# okinesio_v02.net
KiCad netlist of a schematic drawn in EAGLE
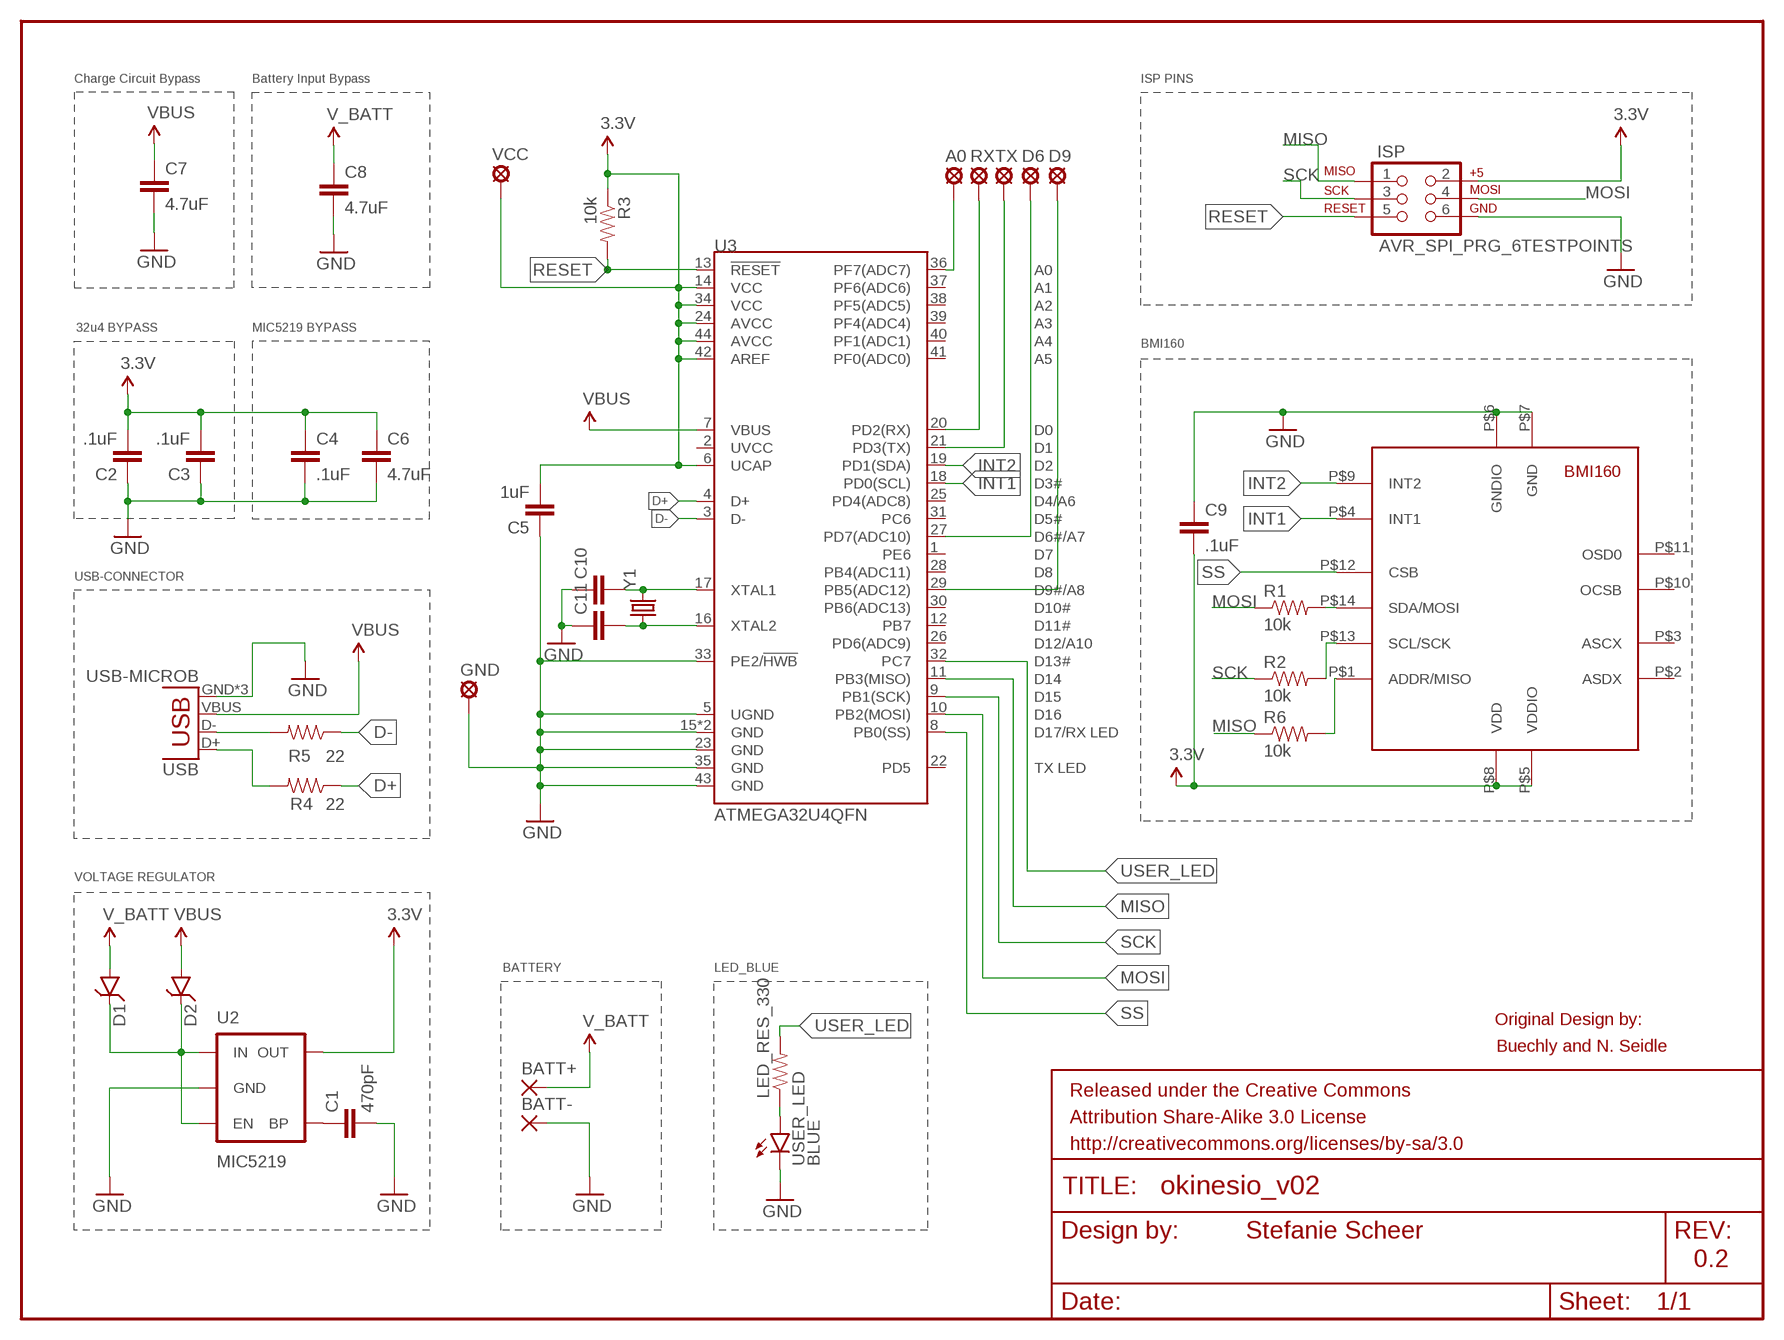
[diagram p0: schematic, sheet 1]

(export (version "E")
  (design (tool "Eeschema 10.0.6"))
  (components
    (comp (ref "A0")
      (value "LSP10")
      (footprint "eagle-import:LSP10")
      (libsource (lib "eagle-import") (part "LSP10"))
    )
    (comp (ref "BATT+")
      (value "SMD2")
      (footprint "eagle-import:SMD1,27-2,54")
      (libsource (lib "eagle-import") (part "SMD2"))
    )
    (comp (ref "BATT-")
      (value "SMD2")
      (footprint "eagle-import:SMD1,27-2,54")
      (libsource (lib "eagle-import") (part "SMD2"))
    )
    (comp (ref "C1")
      (value "470pF")
      (footprint "eagle-import:0603-CAP")
      (libsource (lib "eagle-import") (part "SparkFun-Passives_CAP0603-CAP"))
    )
    (comp (ref "C2")
      (value ".1uF")
      (footprint "eagle-import:0603-CAP")
      (libsource (lib "eagle-import") (part "SparkFun-Passives_CAP0603-CAP"))
    )
    (comp (ref "C3")
      (value ".1uF")
      (footprint "eagle-import:0603-CAP")
      (libsource (lib "eagle-import") (part "SparkFun-Passives_CAP0603-CAP"))
    )
    (comp (ref "C4")
      (value ".1uF")
      (footprint "eagle-import:0603-CAP")
      (libsource (lib "eagle-import") (part "CAP0603-CAP"))
    )
    (comp (ref "C5")
      (value "1uF")
      (footprint "eagle-import:0603-CAP")
      (libsource (lib "eagle-import") (part "SparkFun-Passives_CAP0603-CAP"))
    )
    (comp (ref "C6")
      (value "4.7uF")
      (footprint "eagle-import:0603-CAP")
      (libsource (lib "eagle-import") (part "CAP0603-CAP"))
    )
    (comp (ref "C7")
      (value "4.7uF")
      (footprint "eagle-import:0805")
      (libsource (lib "eagle-import") (part "CAP0805"))
    )
    (comp (ref "C8")
      (value "4.7uF")
      (footprint "eagle-import:0805")
      (libsource (lib "eagle-import") (part "CAP0805"))
    )
    (comp (ref "C9")
      (value ".1uF")
      (footprint "eagle-import:0603-CAP")
      (libsource (lib "eagle-import") (part "SparkFun-Passives_CAP0603-CAP"))
    )
    (comp (ref "C10")
      (value "CAP0603-CAP")
      (footprint "eagle-import:0603-CAP")
      (libsource (lib "eagle-import") (part "CAP0603-CAP"))
    )
    (comp (ref "C11")
      (value "CAP0603-CAP")
      (footprint "eagle-import:0603-CAP")
      (libsource (lib "eagle-import") (part "CAP0603-CAP"))
    )
    (comp (ref "D1")
      (value "DIODESOD123")
      (footprint "eagle-import:SOD-123")
      (libsource (lib "eagle-import") (part "DIODESOD123"))
    )
    (comp (ref "D2")
      (value "DIODESOD123")
      (footprint "eagle-import:SOD-123")
      (libsource (lib "eagle-import") (part "DIODESOD123"))
    )
    (comp (ref "D6")
      (value "LSP10")
      (footprint "eagle-import:LSP10")
      (libsource (lib "eagle-import") (part "LSP10"))
    )
    (comp (ref "D9")
      (value "LSP10")
      (footprint "eagle-import:LSP10")
      (libsource (lib "eagle-import") (part "LSP10"))
    )
    (comp (ref "GND")
      (value "LSP10")
      (footprint "eagle-import:LSP10")
      (libsource (lib "eagle-import") (part "LSP10"))
    )
    (comp (ref "ISP")
      (value "AVR_SPI_PRG_6TESTPOINTS")
      (footprint "eagle-import:2X3_TEST_POINTS")
      (libsource (lib "eagle-import") (part "AVR_SPI_PRG_6TESTPOINTS"))
    )
    (comp (ref "LED_RES_330")
      (value "RESISTOR0603")
      (footprint "eagle-import:0603-RES")
      (libsource (lib "eagle-import") (part "RESISTOR0603"))
    )
    (comp (ref "R1")
      (value "10k")
      (footprint "eagle-import:0603-RES")
      (libsource (lib "eagle-import") (part "RESISTOR0603-RES"))
    )
    (comp (ref "R2")
      (value "10k")
      (footprint "eagle-import:0603-RES")
      (libsource (lib "eagle-import") (part "RESISTOR0603-RES"))
    )
    (comp (ref "R3")
      (value "10k")
      (footprint "eagle-import:0603-RES")
      (libsource (lib "eagle-import") (part "RESISTOR0603-RES"))
    )
    (comp (ref "R4")
      (value "22")
      (footprint "eagle-import:0603-RES")
      (libsource (lib "eagle-import") (part "RESISTOR0603-RES"))
    )
    (comp (ref "R5")
      (value "22")
      (footprint "eagle-import:0603-RES")
      (libsource (lib "eagle-import") (part "RESISTOR0603-RES"))
    )
    (comp (ref "R6")
      (value "10k")
      (footprint "eagle-import:0603-RES")
      (libsource (lib "eagle-import") (part "RESISTOR0603-RES"))
    )
    (comp (ref "RX")
      (value "LSP10")
      (footprint "eagle-import:LSP10")
      (libsource (lib "eagle-import") (part "LSP10"))
    )
    (comp (ref "TX")
      (value "LSP10")
      (footprint "eagle-import:LSP10")
      (libsource (lib "eagle-import") (part "LSP10"))
    )
    (comp (ref "U$3")
      (value "BMI160LGA14")
      (footprint "eagle-import:LGA14-BMI160")
      (libsource (lib "eagle-import") (part "BMI160LGA14"))
    )
    (comp (ref "U2")
      (value "MIC5219")
      (footprint "eagle-import:SOT23-5")
      (libsource (lib "eagle-import") (part "V_REG_MIC5219SMD"))
    )
    (comp (ref "U3")
      (value "ATMEGA32U4QFN")
      (footprint "eagle-import:QFN-44")
      (libsource (lib "eagle-import") (part "ATMEGA32U4QFN"))
    )
    (comp (ref "USB")
      (value "USB-MICROB")
      (footprint "eagle-import:USB-MICROB")
      (libsource (lib "eagle-import") (part "USB-MICROB"))
    )
    (comp (ref "USER_LED")
      (value "BLUE")
      (footprint "eagle-import:LED-0603")
      (libsource (lib "eagle-import") (part "LED-BLUE0603"))
    )
    (comp (ref "VCC")
      (value "LSP10")
      (footprint "eagle-import:LSP10")
      (libsource (lib "eagle-import") (part "LSP10"))
    )
    (comp (ref "Y1")
      (value "CRYSTALTXC-7A")
      (footprint "eagle-import:CRYSTAL-TXC-7A")
      (libsource (lib "eagle-import") (part "CRYSTALTXC-7A"))
    )
  )
  (nets
    (net (code "1") (name "3.3V") (class "Default")
      (node (ref "C2") (pin "2") (pinfunction "2_2") (pintype "passive"))
      (node (ref "C3") (pin "2") (pinfunction "2_2") (pintype "passive"))
      (node (ref "C4") (pin "1") (pinfunction "1_1") (pintype "passive"))
      (node (ref "C5") (pin "2") (pinfunction "2_2") (pintype "passive"))
      (node (ref "C6") (pin "1") (pinfunction "1_1") (pintype "passive"))
      (node (ref "C9") (pin "2") (pinfunction "2_2") (pintype "passive"))
      (node (ref "ISP") (pin "2") (pinfunction "2_2") (pintype "passive"))
      (node (ref "R3") (pin "1") (pinfunction "1_1") (pintype "passive"))
      (node (ref "U$3") (pin "P$5") (pinfunction "VDDIO_P$5") (pintype "bidirectional"))
      (node (ref "U$3") (pin "P$8") (pinfunction "VDD_P$8") (pintype "bidirectional"))
      (node (ref "U2") (pin "5") (pinfunction "OUT_5") (pintype "passive"))
      (node (ref "U3") (pin "14") (pinfunction "VCC_14") (pintype "bidirectional"))
      (node (ref "U3") (pin "24") (pinfunction "AVCC_24") (pintype "bidirectional"))
      (node (ref "U3") (pin "34") (pinfunction "VCC_34") (pintype "bidirectional"))
      (node (ref "U3") (pin "42") (pinfunction "AREF_42") (pintype "bidirectional"))
      (node (ref "U3") (pin "44") (pinfunction "AVCC_44") (pintype "bidirectional"))
      (node (ref "U3") (pin "6") (pinfunction "UCAP_6") (pintype "bidirectional"))
      (node (ref "VCC") (pin "MP") (pinfunction "MP_MP") (pintype "passive"))
    )
    (net (code "2") (name "D+") (class "Default")
      (node (ref "R4") (pin "1") (pinfunction "1_1") (pintype "passive"))
      (node (ref "U3") (pin "4") (pinfunction "D+_4") (pintype "bidirectional"))
    )
    (net (code "3") (name "D-") (class "Default")
      (node (ref "R5") (pin "1") (pinfunction "1_1") (pintype "passive"))
      (node (ref "U3") (pin "3") (pinfunction "D-_3") (pintype "bidirectional"))
    )
    (net (code "4") (name "GND") (class "Default")
      (node (ref "BATT-") (pin "1") (pinfunction "P_1") (pintype "passive"))
      (node (ref "C1") (pin "2") (pinfunction "2_2") (pintype "passive"))
      (node (ref "C10") (pin "1") (pinfunction "1_1") (pintype "passive"))
      (node (ref "C11") (pin "1") (pinfunction "1_1") (pintype "passive"))
      (node (ref "C2") (pin "1") (pinfunction "1_1") (pintype "passive"))
      (node (ref "C3") (pin "1") (pinfunction "1_1") (pintype "passive"))
      (node (ref "C4") (pin "2") (pinfunction "2_2") (pintype "passive"))
      (node (ref "C5") (pin "1") (pinfunction "1_1") (pintype "passive"))
      (node (ref "C6") (pin "2") (pinfunction "2_2") (pintype "passive"))
      (node (ref "C7") (pin "2") (pinfunction "2_2") (pintype "passive"))
      (node (ref "C8") (pin "2") (pinfunction "2_2") (pintype "passive"))
      (node (ref "C9") (pin "1") (pinfunction "1_1") (pintype "passive"))
      (node (ref "GND") (pin "MP") (pinfunction "MP_MP") (pintype "passive"))
      (node (ref "ISP") (pin "6") (pinfunction "6_6") (pintype "passive"))
      (node (ref "U$3") (pin "P$6") (pinfunction "GNDIO_P$6") (pintype "bidirectional"))
      (node (ref "U$3") (pin "P$7") (pinfunction "GND_P$7") (pintype "bidirectional"))
      (node (ref "U2") (pin "2") (pinfunction "GND_2") (pintype "input"))
      (node (ref "U3") (pin "15") (pinfunction "GND_15") (pintype "bidirectional"))
      (node (ref "U3") (pin "23") (pinfunction "GND_23") (pintype "bidirectional"))
      (node (ref "U3") (pin "33") (pinfunction "PE2/~{HWB}_33") (pintype "bidirectional"))
      (node (ref "U3") (pin "35") (pinfunction "GND_35") (pintype "bidirectional"))
      (node (ref "U3") (pin "43") (pinfunction "GND_43") (pintype "bidirectional"))
      (node (ref "U3") (pin "5") (pinfunction "UGND_5") (pintype "bidirectional"))
      (node (ref "U3") (pin "EPAD") (pinfunction "GND_EPAD") (pintype "bidirectional"))
      (node (ref "USB") (pin "GND") (pinfunction "GND_GND") (pintype "bidirectional"))
      (node (ref "USB") (pin "MT1") (pinfunction "GND_MT1") (pintype "bidirectional"))
      (node (ref "USB") (pin "MT2") (pinfunction "GND_MT2") (pintype "bidirectional"))
      (node (ref "USER_LED") (pin "C") (pinfunction "C_C") (pintype "passive"))
    )
    (net (code "5") (name "INT1") (class "Default")
      (node (ref "U$3") (pin "P$4") (pinfunction "INT1_P$4") (pintype "bidirectional"))
      (node (ref "U3") (pin "18") (pinfunction "PD0(SCL)_18") (pintype "bidirectional"))
    )
    (net (code "6") (name "INT2") (class "Default")
      (node (ref "U$3") (pin "P$9") (pinfunction "INT2_P$9") (pintype "bidirectional"))
      (node (ref "U3") (pin "19") (pinfunction "PD1(SDA)_19") (pintype "bidirectional"))
    )
    (net (code "7") (name "MISO") (class "Default")
      (node (ref "ISP") (pin "1") (pinfunction "1_1") (pintype "passive"))
      (node (ref "R6") (pin "1") (pinfunction "1_1") (pintype "passive"))
      (node (ref "U3") (pin "11") (pinfunction "PB3(MISO)_11") (pintype "bidirectional"))
    )
    (net (code "8") (name "MOSI") (class "Default")
      (node (ref "ISP") (pin "4") (pinfunction "4_4") (pintype "passive"))
      (node (ref "R1") (pin "1") (pinfunction "1_1") (pintype "passive"))
      (node (ref "U3") (pin "10") (pinfunction "PB2(MOSI)_10") (pintype "bidirectional"))
    )
    (net (code "9") (name "Net-(LED_RES_330-Pad1)") (class "Default")
      (node (ref "LED_RES_330") (pin "1") (pinfunction "1_1") (pintype "passive"))
      (node (ref "USER_LED") (pin "A") (pinfunction "A_A") (pintype "passive"))
    )
    (net (code "10") (name "Net-(R4-Pad2)") (class "Default")
      (node (ref "R4") (pin "2") (pinfunction "2_2") (pintype "passive"))
      (node (ref "USB") (pin "D+") (pinfunction "D+_D+") (pintype "bidirectional"))
    )
    (net (code "11") (name "Net-(R5-Pad2)") (class "Default")
      (node (ref "R5") (pin "2") (pinfunction "2_2") (pintype "passive"))
      (node (ref "USB") (pin "D-") (pinfunction "D-_D-") (pintype "bidirectional"))
    )
    (net (code "12") (name "Net-(U$3-ADDR{slash}MISO)") (class "Default")
      (node (ref "R6") (pin "2") (pinfunction "2_2") (pintype "passive"))
      (node (ref "U$3") (pin "P$1") (pinfunction "ADDR/MISO_P$1") (pintype "bidirectional"))
    )
    (net (code "13") (name "Net-(U$3-SCL{slash}SCK)") (class "Default")
      (node (ref "R2") (pin "2") (pinfunction "2_2") (pintype "passive"))
      (node (ref "U$3") (pin "P$13") (pinfunction "SCL/SCK_P$13") (pintype "bidirectional"))
    )
    (net (code "14") (name "Net-(U$3-SDA{slash}MOSI)") (class "Default")
      (node (ref "R1") (pin "2") (pinfunction "2_2") (pintype "passive"))
      (node (ref "U$3") (pin "P$14") (pinfunction "SDA/MOSI_P$14") (pintype "bidirectional"))
    )
    (net (code "15") (name "Net-(U2-BP)") (class "Default")
      (node (ref "C1") (pin "1") (pinfunction "1_1") (pintype "passive"))
      (node (ref "U2") (pin "4") (pinfunction "BP_4") (pintype "input"))
    )
    (net (code "16") (name "Net-(U2-EN)") (class "Default")
      (node (ref "D1") (pin "C") (pinfunction "C_C") (pintype "passive"))
      (node (ref "D2") (pin "C") (pinfunction "C_C") (pintype "passive"))
      (node (ref "U2") (pin "1") (pinfunction "IN_1") (pintype "input"))
      (node (ref "U2") (pin "3") (pinfunction "EN_3") (pintype "input"))
    )
    (net (code "17") (name "Net-(U3-PB5(ADC12))") (class "Default")
      (node (ref "D9") (pin "MP") (pinfunction "MP_MP") (pintype "passive"))
      (node (ref "U3") (pin "29") (pinfunction "PB5(ADC12)_29") (pintype "bidirectional"))
    )
    (net (code "18") (name "Net-(U3-PD2(RX))") (class "Default")
      (node (ref "RX") (pin "MP") (pinfunction "MP_MP") (pintype "passive"))
      (node (ref "U3") (pin "20") (pinfunction "PD2(RX)_20") (pintype "bidirectional"))
    )
    (net (code "19") (name "Net-(U3-PD3(TX))") (class "Default")
      (node (ref "TX") (pin "MP") (pinfunction "MP_MP") (pintype "passive"))
      (node (ref "U3") (pin "21") (pinfunction "PD3(TX)_21") (pintype "bidirectional"))
    )
    (net (code "20") (name "Net-(U3-PD7(ADC10))") (class "Default")
      (node (ref "D6") (pin "MP") (pinfunction "MP_MP") (pintype "passive"))
      (node (ref "U3") (pin "27") (pinfunction "PD7(ADC10)_27") (pintype "bidirectional"))
    )
    (net (code "21") (name "Net-(U3-PF7(ADC7))") (class "Default")
      (node (ref "A0") (pin "MP") (pinfunction "MP_MP") (pintype "passive"))
      (node (ref "U3") (pin "36") (pinfunction "PF7(ADC7)_36") (pintype "bidirectional"))
    )
    (net (code "22") (name "Net-(U3-XTAL1)") (class "Default")
      (node (ref "C10") (pin "2") (pinfunction "2_2") (pintype "passive"))
      (node (ref "U3") (pin "17") (pinfunction "XTAL1_17") (pintype "bidirectional"))
      (node (ref "Y1") (pin "P$2") (pinfunction "2_P$2") (pintype "passive"))
    )
    (net (code "23") (name "Net-(U3-XTAL2)") (class "Default")
      (node (ref "C11") (pin "2") (pinfunction "2_2") (pintype "passive"))
      (node (ref "U3") (pin "16") (pinfunction "XTAL2_16") (pintype "bidirectional"))
      (node (ref "Y1") (pin "P$1") (pinfunction "1_P$1") (pintype "passive"))
    )
    (net (code "24") (name "RESET") (class "Default")
      (node (ref "ISP") (pin "5") (pinfunction "5_5") (pintype "passive"))
      (node (ref "R3") (pin "2") (pinfunction "2_2") (pintype "passive"))
      (node (ref "U3") (pin "13") (pinfunction "~{RESET}_13") (pintype "bidirectional"))
    )
    (net (code "25") (name "SCK") (class "Default")
      (node (ref "ISP") (pin "3") (pinfunction "3_3") (pintype "passive"))
      (node (ref "R2") (pin "1") (pinfunction "1_1") (pintype "passive"))
      (node (ref "U3") (pin "9") (pinfunction "PB1(SCK)_9") (pintype "bidirectional"))
    )
    (net (code "26") (name "SS") (class "Default")
      (node (ref "U$3") (pin "P$12") (pinfunction "CSB_P$12") (pintype "bidirectional"))
      (node (ref "U3") (pin "8") (pinfunction "PB0(SS)_8") (pintype "bidirectional"))
    )
    (net (code "27") (name "USER_LED") (class "Default")
      (node (ref "LED_RES_330") (pin "2") (pinfunction "2_2") (pintype "passive"))
      (node (ref "U3") (pin "32") (pinfunction "PC7_32") (pintype "bidirectional"))
    )
    (net (code "28") (name "VBUS") (class "Default")
      (node (ref "C7") (pin "1") (pinfunction "1_1") (pintype "passive"))
      (node (ref "D2") (pin "A") (pinfunction "A_A") (pintype "passive"))
      (node (ref "U3") (pin "7") (pinfunction "VBUS_7") (pintype "bidirectional"))
      (node (ref "USB") (pin "VBUS") (pinfunction "VBUS_VBUS") (pintype "bidirectional"))
    )
    (net (code "29") (name "V_BATT") (class "Default")
      (node (ref "BATT+") (pin "1") (pinfunction "P_1") (pintype "passive"))
      (node (ref "C8") (pin "1") (pinfunction "1_1") (pintype "passive"))
      (node (ref "D1") (pin "A") (pinfunction "A_A") (pintype "passive"))
    )
    (net (code "30") (name "unconnected-(U$3-ASCX-PadP$3)") (class "Default")
      (node (ref "U$3") (pin "P$3") (pinfunction "ASCX_P$3") (pintype "bidirectional"))
    )
    (net (code "31") (name "unconnected-(U$3-ASDX-PadP$2)") (class "Default")
      (node (ref "U$3") (pin "P$2") (pinfunction "ASDX_P$2") (pintype "bidirectional"))
    )
    (net (code "32") (name "unconnected-(U$3-OCSB-PadP$10)") (class "Default")
      (node (ref "U$3") (pin "P$10") (pinfunction "OCSB_P$10") (pintype "bidirectional"))
    )
    (net (code "33") (name "unconnected-(U$3-OSD0-PadP$11)") (class "Default")
      (node (ref "U$3") (pin "P$11") (pinfunction "OSD0_P$11") (pintype "bidirectional"))
    )
    (net (code "34") (name "unconnected-(U3-PB4(ADC11)-Pad28)") (class "Default")
      (node (ref "U3") (pin "28") (pinfunction "PB4(ADC11)_28") (pintype "bidirectional"))
    )
    (net (code "35") (name "unconnected-(U3-PB6(ADC13)-Pad30)") (class "Default")
      (node (ref "U3") (pin "30") (pinfunction "PB6(ADC13)_30") (pintype "bidirectional"))
    )
    (net (code "36") (name "unconnected-(U3-PB7-Pad12)") (class "Default")
      (node (ref "U3") (pin "12") (pinfunction "PB7_12") (pintype "bidirectional"))
    )
    (net (code "37") (name "unconnected-(U3-PC6-Pad31)") (class "Default")
      (node (ref "U3") (pin "31") (pinfunction "PC6_31") (pintype "bidirectional"))
    )
    (net (code "38") (name "unconnected-(U3-PD4(ADC8)-Pad25)") (class "Default")
      (node (ref "U3") (pin "25") (pinfunction "PD4(ADC8)_25") (pintype "bidirectional"))
    )
    (net (code "39") (name "unconnected-(U3-PD5-Pad22)") (class "Default")
      (node (ref "U3") (pin "22") (pinfunction "PD5_22") (pintype "bidirectional"))
    )
    (net (code "40") (name "unconnected-(U3-PD6(ADC9)-Pad26)") (class "Default")
      (node (ref "U3") (pin "26") (pinfunction "PD6(ADC9)_26") (pintype "bidirectional"))
    )
    (net (code "41") (name "unconnected-(U3-PE6-Pad1)") (class "Default")
      (node (ref "U3") (pin "1") (pinfunction "PE6_1") (pintype "bidirectional"))
    )
    (net (code "42") (name "unconnected-(U3-PF0(ADC0)-Pad41)") (class "Default")
      (node (ref "U3") (pin "41") (pinfunction "PF0(ADC0)_41") (pintype "bidirectional"))
    )
    (net (code "43") (name "unconnected-(U3-PF1(ADC1)-Pad40)") (class "Default")
      (node (ref "U3") (pin "40") (pinfunction "PF1(ADC1)_40") (pintype "bidirectional"))
    )
    (net (code "44") (name "unconnected-(U3-PF4(ADC4)-Pad39)") (class "Default")
      (node (ref "U3") (pin "39") (pinfunction "PF4(ADC4)_39") (pintype "bidirectional"))
    )
    (net (code "45") (name "unconnected-(U3-PF5(ADC5)-Pad38)") (class "Default")
      (node (ref "U3") (pin "38") (pinfunction "PF5(ADC5)_38") (pintype "bidirectional"))
    )
    (net (code "46") (name "unconnected-(U3-PF6(ADC6)-Pad37)") (class "Default")
      (node (ref "U3") (pin "37") (pinfunction "PF6(ADC6)_37") (pintype "bidirectional"))
    )
    (net (code "47") (name "unconnected-(U3-UVCC-Pad2)") (class "Default")
      (node (ref "U3") (pin "2") (pinfunction "UVCC_2") (pintype "bidirectional"))
    )
  )
)
